# M3-LCD.net
KiCad netlist of a schematic drawn in Altium Designer
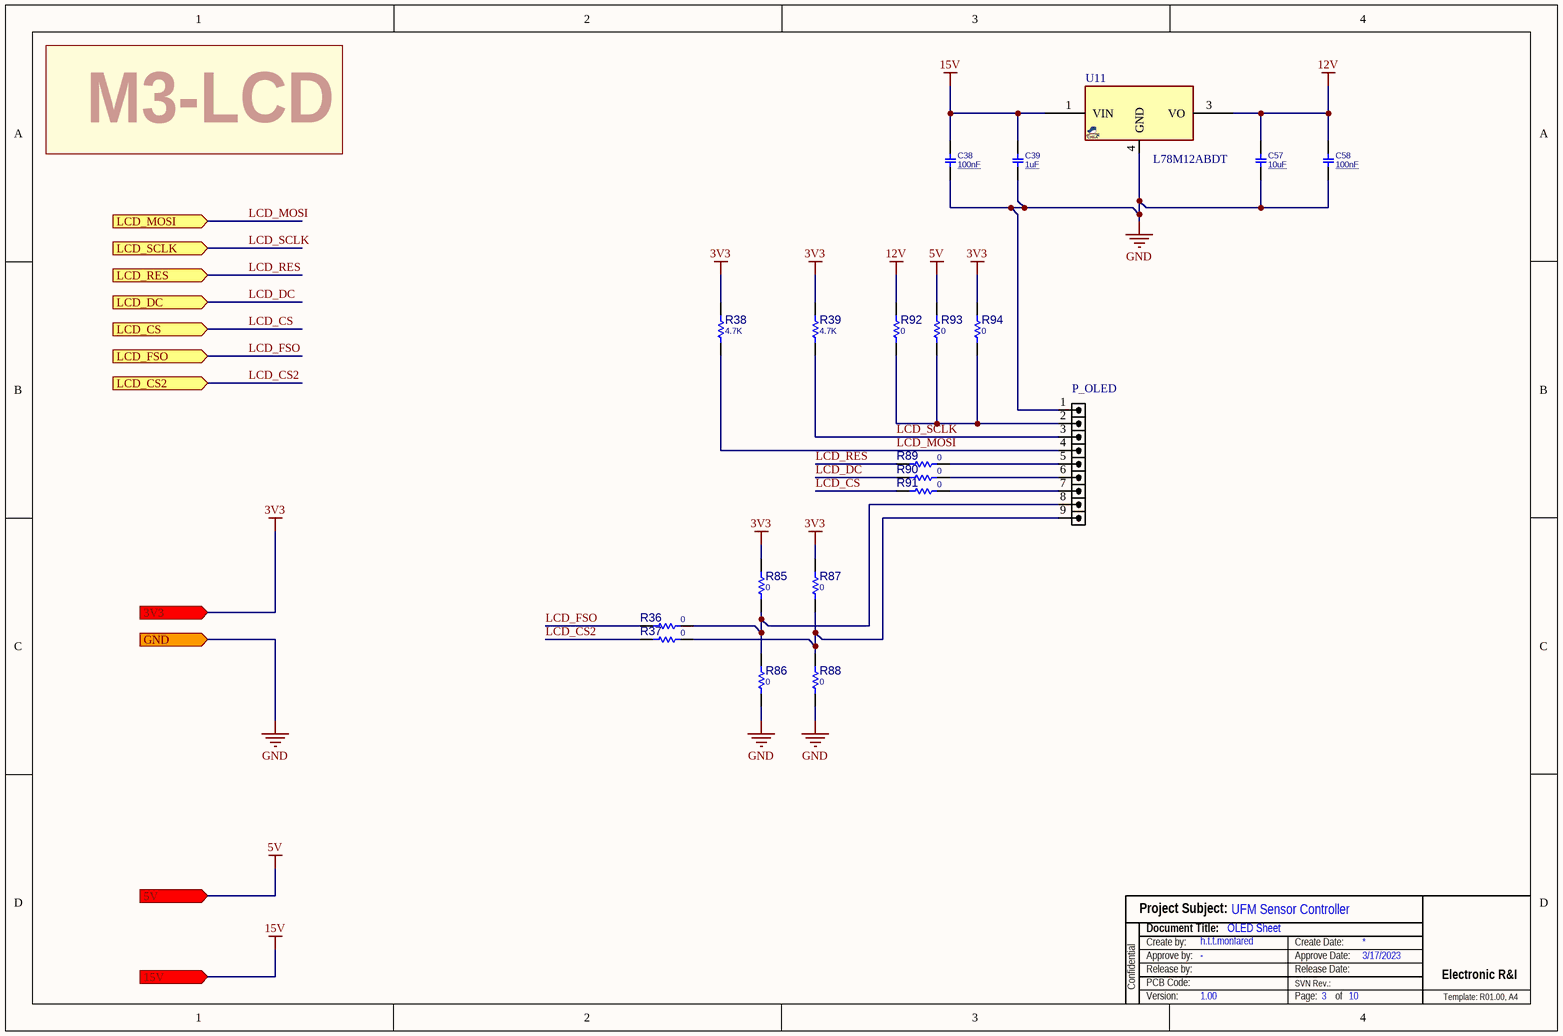
[diagram p0: M3-LCD.SchDoc]

(export (version "E")
  (design (tool "Eeschema 10.0.6"))
  (components
    (comp (ref "C38")
      (value "100nF")
      (footprint "C1206")
      (description "CAP, MLCC, 1nF, 50V, C0G, 10%, 0402")
      (fields (field (name "MANF_P#") "MANF_PART#") (field (name "MANF") "Murata"))
      (libsource (lib "passive_smd") (part "CAP_SMD_MLCC"))
    )
    (comp (ref "C39")
      (value "1uF")
      (footprint "C1206")
      (description "CAP, MLCC, 1nF, 50V, C0G, 10%, 0402")
      (fields (field (name "MANF_P#") "MANF_PART#") (field (name "MANF") "Murata"))
      (libsource (lib "passive_smd") (part "CAP_SMD_MLCC"))
    )
    (comp (ref "C57")
      (value "10uF")
      (footprint "C1206")
      (description "CAP, MLCC, 1nF, 50V, C0G, 10%, 0402")
      (fields (field (name "MANF_P#") "MANF_PART#") (field (name "MANF") "Murata"))
      (libsource (lib "passive_smd") (part "CAP_SMD_MLCC"))
    )
    (comp (ref "C58")
      (value "100nF")
      (footprint "C1206")
      (description "CAP, MLCC, 1nF, 50V, C0G, 10%, 0402")
      (fields (field (name "MANF_P#") "MANF_PART#") (field (name "MANF") "Murata"))
      (libsource (lib "passive_smd") (part "CAP_SMD_MLCC"))
    )
    (comp (ref "P_OLED")
      (value "HDR1X9")
      (footprint "TMS9")
      (description "CONN, HEADER, Male, pitch: 2.54mm, 9POS")
      (libsource (lib "conn_header_2.54mm_st") (part "HDR_M_1X9"))
    )
    (comp (ref "R36")
      (value "0")
      (footprint "R1206")
      (description "RESISTOR, SMD")
      (libsource (lib "passive_smd") (part "RES_SMD"))
    )
    (comp (ref "R37")
      (value "0")
      (footprint "R1206")
      (description "RESISTOR, SMD")
      (libsource (lib "passive_smd") (part "RES_SMD"))
    )
    (comp (ref "R38")
      (value "4.7K")
      (footprint "R1206")
      (description "RESISTOR, SMD")
      (libsource (lib "passive_smd") (part "RES_SMD"))
    )
    (comp (ref "R39")
      (value "4.7K")
      (footprint "R1206")
      (description "RESISTOR, SMD")
      (libsource (lib "passive_smd") (part "RES_SMD"))
    )
    (comp (ref "R85")
      (value "0")
      (footprint "R1206")
      (description "RESISTOR, SMD")
      (libsource (lib "passive_smd") (part "RES_SMD"))
    )
    (comp (ref "R86")
      (value "0")
      (footprint "R1206")
      (description "RESISTOR, SMD")
      (libsource (lib "passive_smd") (part "RES_SMD"))
    )
    (comp (ref "R87")
      (value "0")
      (footprint "R1206")
      (description "RESISTOR, SMD")
      (libsource (lib "passive_smd") (part "RES_SMD"))
    )
    (comp (ref "R88")
      (value "0")
      (footprint "R1206")
      (description "RESISTOR, SMD")
      (libsource (lib "passive_smd") (part "RES_SMD"))
    )
    (comp (ref "R89")
      (value "0")
      (footprint "R1206")
      (description "RESISTOR, SMD")
      (libsource (lib "passive_smd") (part "RES_SMD"))
    )
    (comp (ref "R90")
      (value "0")
      (footprint "R1206")
      (description "RESISTOR, SMD")
      (libsource (lib "passive_smd") (part "RES_SMD"))
    )
    (comp (ref "R91")
      (value "0")
      (footprint "R1206")
      (description "RESISTOR, SMD")
      (libsource (lib "passive_smd") (part "RES_SMD"))
    )
    (comp (ref "R92")
      (value "0")
      (footprint "R1206")
      (description "RESISTOR, SMD")
      (libsource (lib "passive_smd") (part "RES_SMD"))
    )
    (comp (ref "R93")
      (value "0")
      (footprint "R1206")
      (description "RESISTOR, SMD")
      (libsource (lib "passive_smd") (part "RES_SMD"))
    )
    (comp (ref "R94")
      (value "0")
      (footprint "R1206")
      (description "RESISTOR, SMD")
      (libsource (lib "passive_smd") (part "RES_SMD"))
    )
    (comp (ref "U11")
      (value "L78M12ABDT")
      (footprint "DPAK_3")
      (description "REG, Linear, Fixed, 12v, 0.5A, TO-252")
      (fields
        (field (name "MANF_P#") "MC78M12CDT, UA78M12CKV, MC78M12ABDT, L78M12CDT, MC78M12BDT, BA78M12FP, TS78M12CP")
        (field (name "MANF") "TI, ST, ON, ROHM, TS")
      )
      (libsource (lib "pwr_reg_linear_78xx79xx") (part "VREG_78M12_TO252"))
    )
  )
  (nets
    (net (code "1") (name "/LCD_CS") (class "Default")
      (node (ref "R91") (pin "1") (pinfunction "1_1") (pintype "passive"))
    )
    (net (code "2") (name "/LCD_CS2") (class "Default")
      (node (ref "R37") (pin "2") (pinfunction "2_2") (pintype "passive"))
    )
    (net (code "3") (name "/LCD_DC") (class "Default")
      (node (ref "R90") (pin "1") (pinfunction "1_1") (pintype "passive"))
    )
    (net (code "4") (name "/LCD_FSO") (class "Default")
      (node (ref "R36") (pin "2") (pinfunction "2_2") (pintype "passive"))
    )
    (net (code "5") (name "/LCD_MOSI") (class "Default")
      (node (ref "P_OLED") (pin "4") (pinfunction "4_4") (pintype "passive"))
      (node (ref "R38") (pin "2") (pinfunction "2_2") (pintype "passive"))
    )
    (net (code "6") (name "/LCD_RES") (class "Default")
      (node (ref "R89") (pin "1") (pinfunction "1_1") (pintype "passive"))
    )
    (net (code "7") (name "/LCD_SCLK") (class "Default")
      (node (ref "P_OLED") (pin "3") (pinfunction "3_3") (pintype "passive"))
      (node (ref "R39") (pin "2") (pinfunction "2_2") (pintype "passive"))
    )
    (net (code "8") (name "3V3") (class "Default")
      (node (ref "R38") (pin "1") (pinfunction "1_1") (pintype "passive"))
      (node (ref "R39") (pin "1") (pinfunction "1_1") (pintype "passive"))
      (node (ref "R85") (pin "2") (pinfunction "2_2") (pintype "passive"))
      (node (ref "R87") (pin "2") (pinfunction "2_2") (pintype "passive"))
      (node (ref "R94") (pin "2") (pinfunction "2_2") (pintype "passive"))
    )
    (net (code "9") (name "5V") (class "Default")
      (node (ref "R93") (pin "2") (pinfunction "2_2") (pintype "passive"))
    )
    (net (code "10") (name "12V") (class "Default")
      (node (ref "C57") (pin "2") (pinfunction "2_2") (pintype "passive"))
      (node (ref "C58") (pin "2") (pinfunction "2_2") (pintype "passive"))
      (node (ref "R92") (pin "2") (pinfunction "2_2") (pintype "passive"))
      (node (ref "U11") (pin "3") (pinfunction "VO_3") (pintype "passive"))
    )
    (net (code "11") (name "15V") (class "Default")
      (node (ref "C38") (pin "2") (pinfunction "2_2") (pintype "passive"))
      (node (ref "C39") (pin "2") (pinfunction "2_2") (pintype "passive"))
      (node (ref "U11") (pin "1") (pinfunction "VIN_1") (pintype "passive"))
    )
    (net (code "12") (name "GND") (class "Default")
      (node (ref "C38") (pin "1") (pinfunction "1_1") (pintype "passive"))
      (node (ref "C39") (pin "1") (pinfunction "1_1") (pintype "passive"))
      (node (ref "C57") (pin "1") (pinfunction "1_1") (pintype "passive"))
      (node (ref "C58") (pin "1") (pinfunction "1_1") (pintype "passive"))
      (node (ref "P_OLED") (pin "1") (pinfunction "1_1") (pintype "passive"))
      (node (ref "R86") (pin "1") (pinfunction "1_1") (pintype "passive"))
      (node (ref "R88") (pin "1") (pinfunction "1_1") (pintype "passive"))
      (node (ref "U11") (pin "4") (pinfunction "GND_4") (pintype "passive"))
    )
    (net (code "13") (name "Net-(P_OLED-Pad2)") (class "Default")
      (node (ref "P_OLED") (pin "2") (pinfunction "2_2") (pintype "passive"))
      (node (ref "R92") (pin "1") (pinfunction "1_1") (pintype "passive"))
      (node (ref "R93") (pin "1") (pinfunction "1_1") (pintype "passive"))
      (node (ref "R94") (pin "1") (pinfunction "1_1") (pintype "passive"))
    )
    (net (code "14") (name "Net-(P_OLED-Pad5)") (class "Default")
      (node (ref "P_OLED") (pin "5") (pinfunction "5_5") (pintype "passive"))
      (node (ref "R89") (pin "2") (pinfunction "2_2") (pintype "passive"))
    )
    (net (code "15") (name "Net-(P_OLED-Pad6)") (class "Default")
      (node (ref "P_OLED") (pin "6") (pinfunction "6_6") (pintype "passive"))
      (node (ref "R90") (pin "2") (pinfunction "2_2") (pintype "passive"))
    )
    (net (code "16") (name "Net-(P_OLED-Pad7)") (class "Default")
      (node (ref "P_OLED") (pin "7") (pinfunction "7_7") (pintype "passive"))
      (node (ref "R91") (pin "2") (pinfunction "2_2") (pintype "passive"))
    )
    (net (code "17") (name "Net-(P_OLED-Pad8)") (class "Default")
      (node (ref "P_OLED") (pin "8") (pinfunction "8_8") (pintype "passive"))
      (node (ref "R36") (pin "1") (pinfunction "1_1") (pintype "passive"))
      (node (ref "R85") (pin "1") (pinfunction "1_1") (pintype "passive"))
      (node (ref "R86") (pin "2") (pinfunction "2_2") (pintype "passive"))
    )
    (net (code "18") (name "Net-(P_OLED-Pad9)") (class "Default")
      (node (ref "P_OLED") (pin "9") (pinfunction "9_9") (pintype "passive"))
      (node (ref "R37") (pin "1") (pinfunction "1_1") (pintype "passive"))
      (node (ref "R87") (pin "1") (pinfunction "1_1") (pintype "passive"))
      (node (ref "R88") (pin "2") (pinfunction "2_2") (pintype "passive"))
    )
  )
)
